# rn2483-moteino.net
KiCad netlist of a schematic drawn in EAGLE
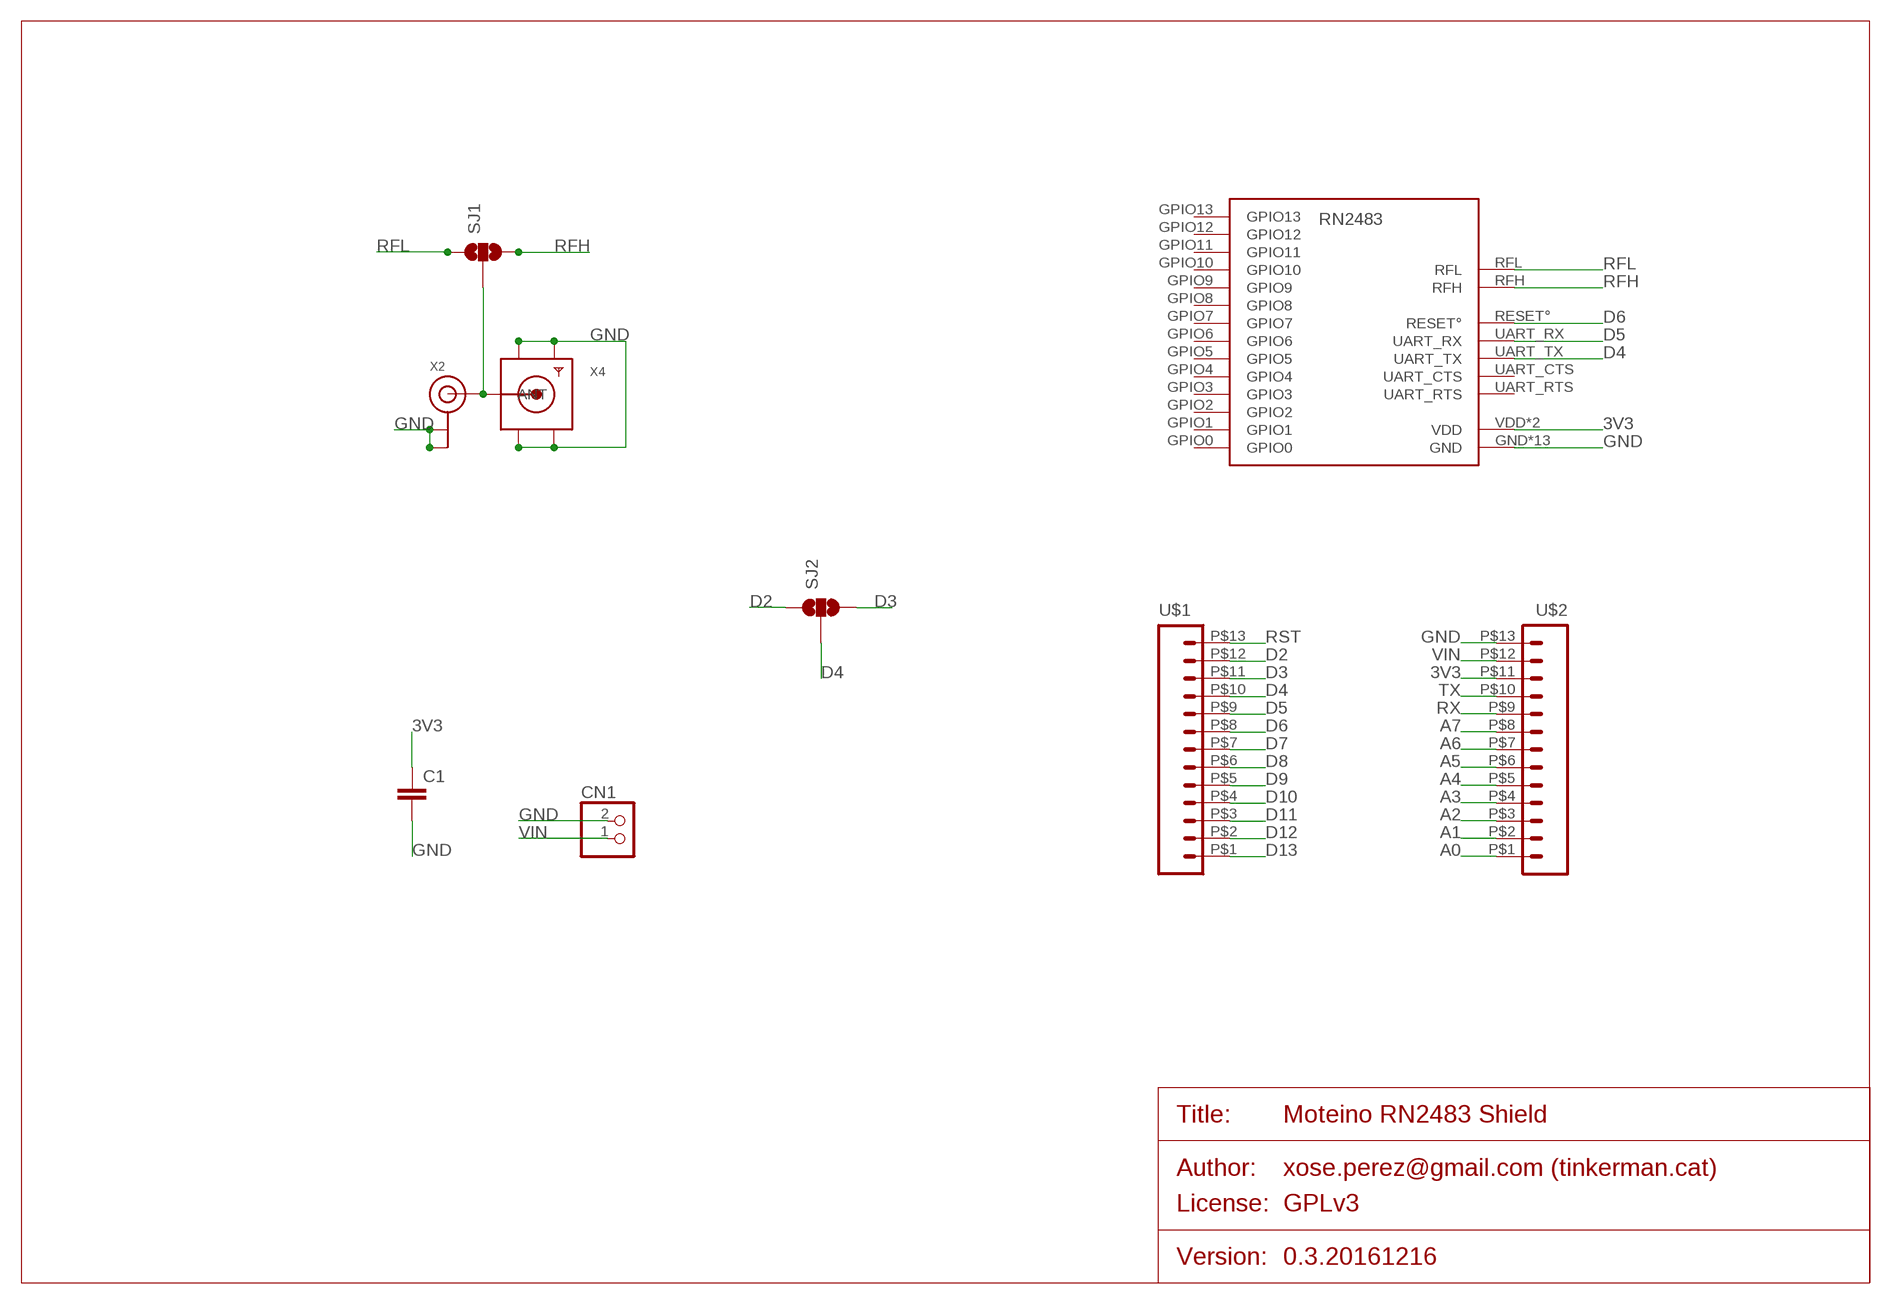
[diagram p0: schematic, sheet 1]

(export (version "E")
  (design (tool "Eeschema 10.0.6"))
  (components
    (comp (ref "C1")
      (value "C-EU0805")
      (footprint "eagle-import:0805")
      (libsource (lib "eagle-import") (part "C-EU0805"))
    )
    (comp (ref "CN1")
      (value "JST_2PIN-SMT-RA")
      (footprint "eagle-import:JST-PH-2-SMT-RA")
      (libsource (lib "eagle-import") (part "JST_2PIN-SMT-RA"))
    )
    (comp (ref "RN2483")
      (value "RN2483ALLPINS")
      (footprint "eagle-import:RN2483")
      (libsource (lib "eagle-import") (part "RN2483ALLPINS"))
    )
    (comp (ref "SJ1")
      (value "SOLDERJUMPER_2WAYS")
      (footprint "eagle-import:SJ_3")
      (libsource (lib "eagle-import") (part "SOLDERJUMPER_2WAYS"))
    )
    (comp (ref "SJ2")
      (value "SOLDERJUMPER_2WAYS")
      (footprint "eagle-import:SJ_3")
      (libsource (lib "eagle-import") (part "SOLDERJUMPER_2WAYS"))
    )
    (comp (ref "U$1")
      (value "M13M13_1X13_SMD")
      (footprint "eagle-import:1X13_SMD")
      (libsource (lib "eagle-import") (part "M13M13_1X13_SMD"))
    )
    (comp (ref "U$2")
      (value "M13M13_1X13_SMD")
      (footprint "eagle-import:1X13_SMD")
      (libsource (lib "eagle-import") (part "M13M13_1X13_SMD"))
    )
    (comp (ref "X2")
      (value "ANTENNA_U.FL")
      (footprint "eagle-import:U.FL")
      (libsource (lib "eagle-import") (part "ANTENNA_U.FL"))
    )
    (comp (ref "X4")
      (value "SMACONNECTOR_EDGE")
      (footprint "eagle-import:SMA_EDGELAUNCH")
      (libsource (lib "eagle-import") (part "SMACONNECTOR_EDGE"))
    )
  )
  (nets
    (net (code "1") (name "/3V3") (class "Default")
      (node (ref "C1") (pin "1") (pinfunction "1_1") (pintype "passive"))
      (node (ref "RN2483") (pin "VDD") (pinfunction "VDD_VDD") (pintype "bidirectional"))
      (node (ref "RN2483") (pin "VDD2") (pinfunction "VDD_VDD2") (pintype "bidirectional"))
      (node (ref "U$2") (pin "P$11") (pinfunction "11_P$11") (pintype "passive"))
    )
    (net (code "2") (name "/A0") (class "Default")
      (node (ref "U$2") (pin "P$1") (pinfunction "1_P$1") (pintype "passive"))
    )
    (net (code "3") (name "/A1") (class "Default")
      (node (ref "U$2") (pin "P$2") (pinfunction "2_P$2") (pintype "passive"))
    )
    (net (code "4") (name "/A2") (class "Default")
      (node (ref "U$2") (pin "P$3") (pinfunction "3_P$3") (pintype "passive"))
    )
    (net (code "5") (name "/A3") (class "Default")
      (node (ref "U$2") (pin "P$4") (pinfunction "4_P$4") (pintype "passive"))
    )
    (net (code "6") (name "/A4") (class "Default")
      (node (ref "U$2") (pin "P$5") (pinfunction "5_P$5") (pintype "passive"))
    )
    (net (code "7") (name "/A5") (class "Default")
      (node (ref "U$2") (pin "P$6") (pinfunction "6_P$6") (pintype "passive"))
    )
    (net (code "8") (name "/A6") (class "Default")
      (node (ref "U$2") (pin "P$7") (pinfunction "7_P$7") (pintype "passive"))
    )
    (net (code "9") (name "/A7") (class "Default")
      (node (ref "U$2") (pin "P$8") (pinfunction "8_P$8") (pintype "passive"))
    )
    (net (code "10") (name "/D2") (class "Default")
      (node (ref "SJ2") (pin "1") (pinfunction "1_1") (pintype "passive"))
      (node (ref "U$1") (pin "P$12") (pinfunction "12_P$12") (pintype "passive"))
    )
    (net (code "11") (name "/D3") (class "Default")
      (node (ref "SJ2") (pin "3") (pinfunction "3_3") (pintype "passive"))
      (node (ref "U$1") (pin "P$11") (pinfunction "11_P$11") (pintype "passive"))
    )
    (net (code "12") (name "/D4") (class "Default")
      (node (ref "RN2483") (pin "UART_TX") (pinfunction "UART_TX_UART_TX") (pintype "bidirectional"))
      (node (ref "SJ2") (pin "2") (pinfunction "2_2") (pintype "passive"))
      (node (ref "U$1") (pin "P$10") (pinfunction "10_P$10") (pintype "passive"))
    )
    (net (code "13") (name "/D5") (class "Default")
      (node (ref "RN2483") (pin "UART_RX") (pinfunction "UART_RX_UART_RX") (pintype "bidirectional"))
      (node (ref "U$1") (pin "P$9") (pinfunction "9_P$9") (pintype "passive"))
    )
    (net (code "14") (name "/D6") (class "Default")
      (node (ref "RN2483") (pin "RESET°") (pinfunction "RESET°_RESET°") (pintype "bidirectional"))
      (node (ref "U$1") (pin "P$8") (pinfunction "8_P$8") (pintype "passive"))
    )
    (net (code "15") (name "/D7") (class "Default")
      (node (ref "U$1") (pin "P$7") (pinfunction "7_P$7") (pintype "passive"))
    )
    (net (code "16") (name "/D8") (class "Default")
      (node (ref "U$1") (pin "P$6") (pinfunction "6_P$6") (pintype "passive"))
    )
    (net (code "17") (name "/D9") (class "Default")
      (node (ref "U$1") (pin "P$5") (pinfunction "5_P$5") (pintype "passive"))
    )
    (net (code "18") (name "/D10") (class "Default")
      (node (ref "U$1") (pin "P$4") (pinfunction "4_P$4") (pintype "passive"))
    )
    (net (code "19") (name "/D11") (class "Default")
      (node (ref "U$1") (pin "P$3") (pinfunction "3_P$3") (pintype "passive"))
    )
    (net (code "20") (name "/D12") (class "Default")
      (node (ref "U$1") (pin "P$2") (pinfunction "2_P$2") (pintype "passive"))
    )
    (net (code "21") (name "/D13") (class "Default")
      (node (ref "U$1") (pin "P$1") (pinfunction "1_P$1") (pintype "passive"))
    )
    (net (code "22") (name "/GND") (class "Default")
      (node (ref "C1") (pin "2") (pinfunction "2_2") (pintype "passive"))
      (node (ref "CN1") (pin "2") (pinfunction "1_2") (pintype "passive"))
      (node (ref "RN2483") (pin "GND") (pinfunction "GND_GND") (pintype "bidirectional"))
      (node (ref "RN2483") (pin "GND1") (pinfunction "GND_GND1") (pintype "bidirectional"))
      (node (ref "RN2483") (pin "GND10") (pinfunction "GND_GND10") (pintype "bidirectional"))
      (node (ref "RN2483") (pin "GND11") (pinfunction "GND_GND11") (pintype "bidirectional"))
      (node (ref "RN2483") (pin "GND12") (pinfunction "GND_GND12") (pintype "bidirectional"))
      (node (ref "RN2483") (pin "GND2") (pinfunction "GND_GND2") (pintype "bidirectional"))
      (node (ref "RN2483") (pin "GND3") (pinfunction "GND_GND3") (pintype "bidirectional"))
      (node (ref "RN2483") (pin "GND4") (pinfunction "GND_GND4") (pintype "bidirectional"))
      (node (ref "RN2483") (pin "GND5") (pinfunction "GND_GND5") (pintype "bidirectional"))
      (node (ref "RN2483") (pin "GND6") (pinfunction "GND_GND6") (pintype "bidirectional"))
      (node (ref "RN2483") (pin "GND7") (pinfunction "GND_GND7") (pintype "bidirectional"))
      (node (ref "RN2483") (pin "GND8") (pinfunction "GND_GND8") (pintype "bidirectional"))
      (node (ref "RN2483") (pin "GND9") (pinfunction "GND_GND9") (pintype "bidirectional"))
      (node (ref "U$2") (pin "P$13") (pinfunction "13_P$13") (pintype "passive"))
      (node (ref "X2") (pin "1") (pinfunction "GND_1") (pintype "passive"))
      (node (ref "X2") (pin "2") (pinfunction "GND_2") (pintype "passive"))
      (node (ref "X4") (pin "GND@1") (pinfunction "GND4_GND@1") (pintype "power_in"))
      (node (ref "X4") (pin "GND@2") (pinfunction "GND3_GND@2") (pintype "power_in"))
      (node (ref "X4") (pin "GND@3") (pinfunction "GND2_GND@3") (pintype "power_in"))
      (node (ref "X4") (pin "GND@4") (pinfunction "GND1_GND@4") (pintype "power_in"))
    )
    (net (code "23") (name "/RFH") (class "Default")
      (node (ref "RN2483") (pin "RFH") (pinfunction "RFH_RFH") (pintype "bidirectional"))
      (node (ref "SJ1") (pin "3") (pinfunction "3_3") (pintype "passive"))
    )
    (net (code "24") (name "/RFL") (class "Default")
      (node (ref "RN2483") (pin "RFL") (pinfunction "RFL_RFL") (pintype "bidirectional"))
      (node (ref "SJ1") (pin "1") (pinfunction "1_1") (pintype "passive"))
    )
    (net (code "25") (name "/RST") (class "Default")
      (node (ref "U$1") (pin "P$13") (pinfunction "13_P$13") (pintype "passive"))
    )
    (net (code "26") (name "/RX") (class "Default")
      (node (ref "U$2") (pin "P$9") (pinfunction "9_P$9") (pintype "passive"))
    )
    (net (code "27") (name "/TX") (class "Default")
      (node (ref "U$2") (pin "P$10") (pinfunction "10_P$10") (pintype "passive"))
    )
    (net (code "28") (name "/VIN") (class "Default")
      (node (ref "CN1") (pin "1") (pinfunction "2_1") (pintype "passive"))
      (node (ref "U$2") (pin "P$12") (pinfunction "12_P$12") (pintype "passive"))
    )
    (net (code "29") (name "Net-(X2-SIGNAL)") (class "Default")
      (node (ref "SJ1") (pin "2") (pinfunction "2_2") (pintype "passive"))
      (node (ref "X2") (pin "3") (pinfunction "SIGNAL_3") (pintype "passive"))
      (node (ref "X4") (pin "P") (pinfunction "ANT_P") (pintype "bidirectional"))
    )
    (net (code "30") (name "unconnected-(RN2483-PadGPIO0)") (class "Default")
      (node (ref "RN2483") (pin "GPIO0") (pinfunction "GPIO0_GPIO0") (pintype "bidirectional"))
    )
    (net (code "31") (name "unconnected-(RN2483-PadGPIO1)") (class "Default")
      (node (ref "RN2483") (pin "GPIO1") (pinfunction "GPIO1_GPIO1") (pintype "bidirectional"))
    )
    (net (code "32") (name "unconnected-(RN2483-PadGPIO2)") (class "Default")
      (node (ref "RN2483") (pin "GPIO2") (pinfunction "GPIO2_GPIO2") (pintype "bidirectional"))
    )
    (net (code "33") (name "unconnected-(RN2483-PadGPIO3)") (class "Default")
      (node (ref "RN2483") (pin "GPIO3") (pinfunction "GPIO3_GPIO3") (pintype "bidirectional"))
    )
    (net (code "34") (name "unconnected-(RN2483-PadGPIO4)") (class "Default")
      (node (ref "RN2483") (pin "GPIO4") (pinfunction "GPIO4_GPIO4") (pintype "bidirectional"))
    )
    (net (code "35") (name "unconnected-(RN2483-PadGPIO5)") (class "Default")
      (node (ref "RN2483") (pin "GPIO5") (pinfunction "GPIO5_GPIO5") (pintype "bidirectional"))
    )
    (net (code "36") (name "unconnected-(RN2483-PadGPIO6)") (class "Default")
      (node (ref "RN2483") (pin "GPIO6") (pinfunction "GPIO6_GPIO6") (pintype "bidirectional"))
    )
    (net (code "37") (name "unconnected-(RN2483-PadGPIO7)") (class "Default")
      (node (ref "RN2483") (pin "GPIO7") (pinfunction "GPIO7_GPIO7") (pintype "bidirectional"))
    )
    (net (code "38") (name "unconnected-(RN2483-PadGPIO8)") (class "Default")
      (node (ref "RN2483") (pin "GPIO8") (pinfunction "GPIO8_GPIO8") (pintype "bidirectional"))
    )
    (net (code "39") (name "unconnected-(RN2483-PadGPIO9)") (class "Default")
      (node (ref "RN2483") (pin "GPIO9") (pinfunction "GPIO9_GPIO9") (pintype "bidirectional"))
    )
    (net (code "40") (name "unconnected-(RN2483-PadGPIO10)") (class "Default")
      (node (ref "RN2483") (pin "GPIO10") (pinfunction "GPIO10_GPIO10") (pintype "bidirectional"))
    )
    (net (code "41") (name "unconnected-(RN2483-PadGPIO11)") (class "Default")
      (node (ref "RN2483") (pin "GPIO11") (pinfunction "GPIO11_GPIO11") (pintype "bidirectional"))
    )
    (net (code "42") (name "unconnected-(RN2483-PadGPIO12)") (class "Default")
      (node (ref "RN2483") (pin "GPIO12") (pinfunction "GPIO12_GPIO12") (pintype "bidirectional"))
    )
    (net (code "43") (name "unconnected-(RN2483-PadGPIO13)") (class "Default")
      (node (ref "RN2483") (pin "GPIO13") (pinfunction "GPIO13_GPIO13") (pintype "bidirectional"))
    )
    (net (code "44") (name "unconnected-(RN2483-PadUART_CTS)") (class "Default")
      (node (ref "RN2483") (pin "UART_CTS") (pinfunction "UART_CTS_UART_CTS") (pintype "bidirectional"))
    )
    (net (code "45") (name "unconnected-(RN2483-PadUART_RTS)") (class "Default")
      (node (ref "RN2483") (pin "UART_RTS") (pinfunction "UART_RTS_UART_RTS") (pintype "bidirectional"))
    )
  )
)
